# PWR_BUCK.net
KiCad netlist of a schematic drawn in Altium Designer
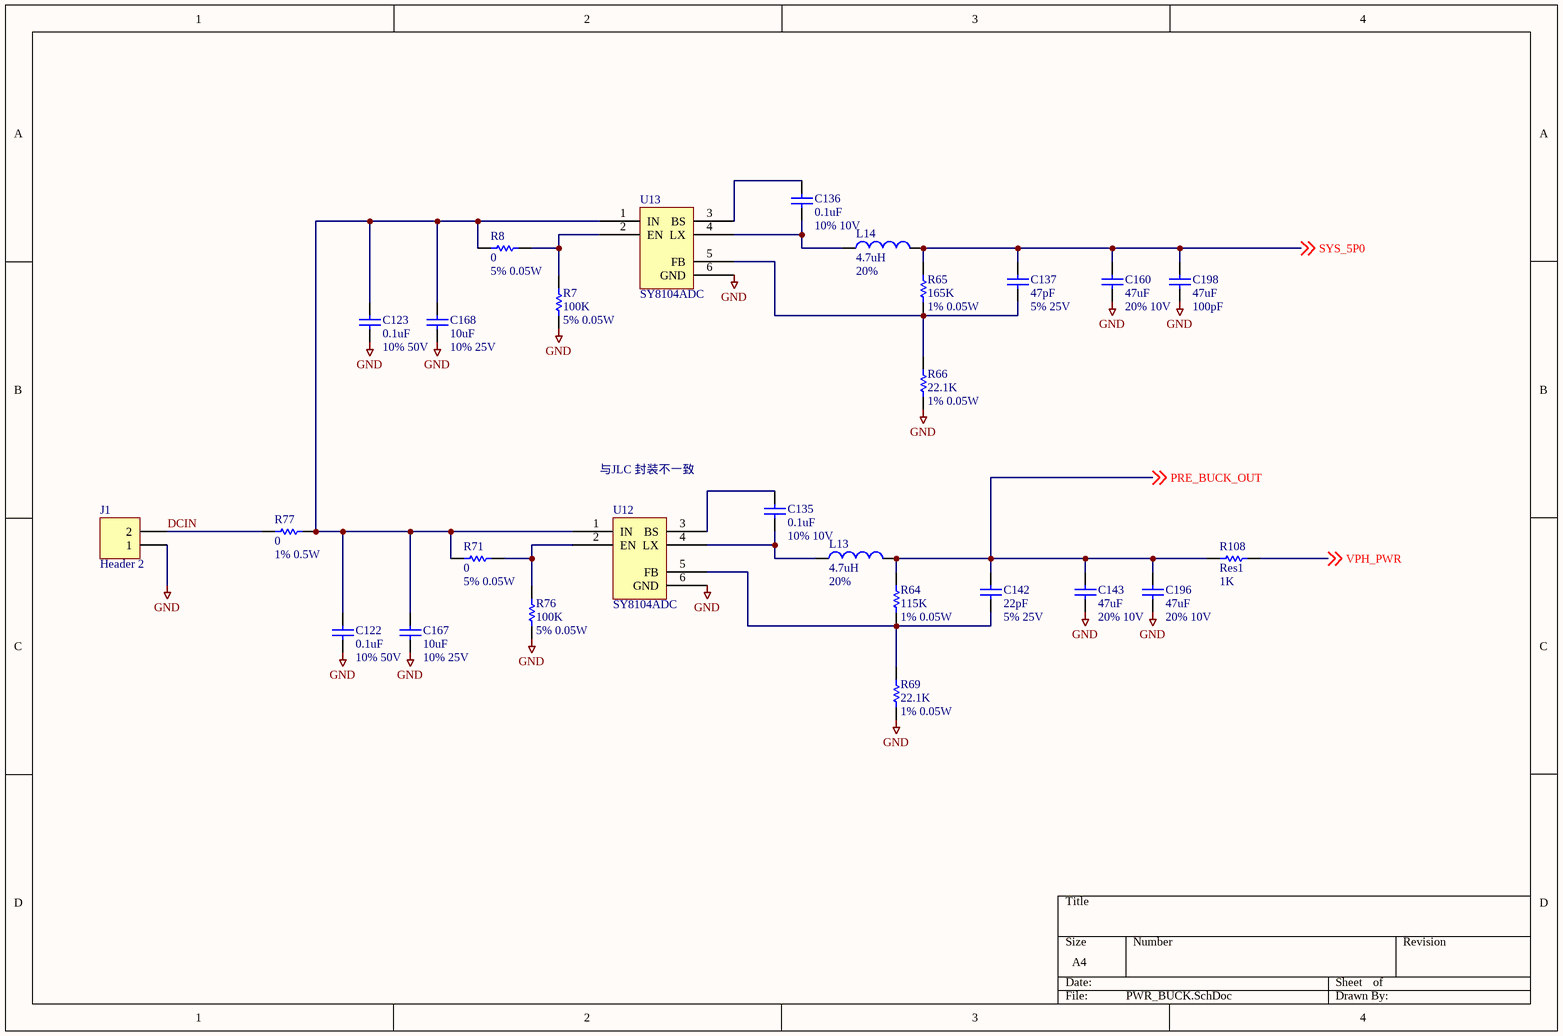
[diagram p0: PWR_BUCK.SchDoc]

(export (version "E")
  (design (tool "Eeschema 10.0.6"))
  (components
    (comp (ref "C122")
      (value "0.1uF")
      (footprint "RAD-0.3")
      (description "Capacitor")
      (fields (field (name "ALTIUM_VALUE") "10% 50V") (field (name "PUBLISHER") "Altium Limited"))
      (libsource (lib "Miscellaneous Devices") (part "Cap"))
    )
    (comp (ref "C123")
      (value "0.1uF")
      (footprint "RAD-0.3")
      (description "Capacitor")
      (fields (field (name "ALTIUM_VALUE") "10% 50V") (field (name "PUBLISHER") "Altium Limited"))
      (libsource (lib "Miscellaneous Devices") (part "Cap"))
    )
    (comp (ref "C135")
      (value "0.1uF")
      (footprint "RAD-0.3")
      (description "Capacitor")
      (fields (field (name "ALTIUM_VALUE") "10% 10V") (field (name "PUBLISHER") "Altium Limited"))
      (libsource (lib "Miscellaneous Devices") (part "Cap"))
    )
    (comp (ref "C136")
      (value "0.1uF")
      (footprint "RAD-0.3")
      (description "Capacitor")
      (fields (field (name "ALTIUM_VALUE") "10% 10V") (field (name "PUBLISHER") "Altium Limited"))
      (libsource (lib "Miscellaneous Devices") (part "Cap"))
    )
    (comp (ref "C137")
      (value "47pF")
      (footprint "RAD-0.3")
      (description "Capacitor")
      (fields (field (name "ALTIUM_VALUE") "5% 25V") (field (name "PUBLISHER") "Altium Limited"))
      (libsource (lib "Miscellaneous Devices") (part "Cap"))
    )
    (comp (ref "C142")
      (value "22pF")
      (footprint "RAD-0.3")
      (description "Capacitor")
      (fields (field (name "ALTIUM_VALUE") "5% 25V") (field (name "PUBLISHER") "Altium Limited"))
      (libsource (lib "Miscellaneous Devices") (part "Cap"))
    )
    (comp (ref "C143")
      (value "47uF")
      (footprint "RAD-0.3")
      (description "Capacitor")
      (fields (field (name "ALTIUM_VALUE") "20% 10V") (field (name "PUBLISHER") "Altium Limited"))
      (libsource (lib "Miscellaneous Devices") (part "Cap"))
    )
    (comp (ref "C160")
      (value "47uF")
      (footprint "RAD-0.3")
      (description "Capacitor")
      (fields (field (name "ALTIUM_VALUE") "20% 10V") (field (name "PUBLISHER") "Altium Limited"))
      (libsource (lib "Miscellaneous Devices") (part "Cap"))
    )
    (comp (ref "C167")
      (value "10uF")
      (footprint "RAD-0.3")
      (description "Capacitor")
      (fields (field (name "ALTIUM_VALUE") "10% 25V") (field (name "PUBLISHER") "Altium Limited"))
      (libsource (lib "Miscellaneous Devices") (part "Cap"))
    )
    (comp (ref "C168")
      (value "10uF")
      (footprint "RAD-0.3")
      (description "Capacitor")
      (fields (field (name "ALTIUM_VALUE") "10% 25V") (field (name "PUBLISHER") "Altium Limited"))
      (libsource (lib "Miscellaneous Devices") (part "Cap"))
    )
    (comp (ref "C196")
      (value "47uF")
      (footprint "RAD-0.3")
      (description "Capacitor")
      (fields (field (name "ALTIUM_VALUE") "20% 10V") (field (name "PUBLISHER") "Altium Limited"))
      (libsource (lib "Miscellaneous Devices") (part "Cap"))
    )
    (comp (ref "C198")
      (value "47uF")
      (footprint "RAD-0.3")
      (description "Capacitor")
      (fields (field (name "ALTIUM_VALUE") "100pF") (field (name "PUBLISHER") "Altium Limited"))
      (libsource (lib "Miscellaneous Devices") (part "Cap"))
    )
    (comp (ref "J1")
      (value "Header 2")
      (footprint "HDR1X2")
      (description "Header, 2-Pin")
      (fields (field (name "PUBLISHER") "Altium Limited"))
      (libsource (lib "Miscellaneous Connectors") (part "Header 2"))
    )
    (comp (ref "L13")
      (value "4.7uH")
      (footprint "0402-A")
      (description "Inductor")
      (fields (field (name "ALTIUM_VALUE") "20%") (field (name "PUBLISHER") "Altium Limited"))
      (libsource (lib "Miscellaneous Devices") (part "Inductor"))
    )
    (comp (ref "L14")
      (value "4.7uH")
      (footprint "0402-A")
      (description "Inductor")
      (fields (field (name "ALTIUM_VALUE") "20%") (field (name "PUBLISHER") "Altium Limited"))
      (libsource (lib "Miscellaneous Devices") (part "Inductor"))
    )
    (comp (ref "R7")
      (value "100K")
      (footprint "AXIAL-0.3")
      (description "Resistor")
      (fields (field (name "ALTIUM_VALUE") "5% 0.05W") (field (name "PUBLISHER") "Altium Limited"))
      (libsource (lib "Miscellaneous Devices") (part "Res1"))
    )
    (comp (ref "R8")
      (value "0")
      (footprint "AXIAL-0.3")
      (description "Resistor")
      (fields (field (name "ALTIUM_VALUE") "5% 0.05W") (field (name "PUBLISHER") "Altium Limited"))
      (libsource (lib "Miscellaneous Devices") (part "Res1"))
    )
    (comp (ref "R64")
      (value "115K")
      (footprint "AXIAL-0.3")
      (description "Resistor")
      (fields (field (name "ALTIUM_VALUE") "1% 0.05W") (field (name "PUBLISHER") "Altium Limited"))
      (libsource (lib "Miscellaneous Devices") (part "Res1"))
    )
    (comp (ref "R65")
      (value "165K")
      (footprint "AXIAL-0.3")
      (description "Resistor")
      (fields (field (name "ALTIUM_VALUE") "1% 0.05W") (field (name "PUBLISHER") "Altium Limited"))
      (libsource (lib "Miscellaneous Devices") (part "Res1"))
    )
    (comp (ref "R66")
      (value "22.1K")
      (footprint "AXIAL-0.3")
      (description "Resistor")
      (fields (field (name "ALTIUM_VALUE") "1% 0.05W") (field (name "PUBLISHER") "Altium Limited"))
      (libsource (lib "Miscellaneous Devices") (part "Res1"))
    )
    (comp (ref "R69")
      (value "22.1K")
      (footprint "AXIAL-0.3")
      (description "Resistor")
      (fields (field (name "ALTIUM_VALUE") "1% 0.05W") (field (name "PUBLISHER") "Altium Limited"))
      (libsource (lib "Miscellaneous Devices") (part "Res1"))
    )
    (comp (ref "R71")
      (value "0")
      (footprint "AXIAL-0.3")
      (description "Resistor")
      (fields (field (name "ALTIUM_VALUE") "5% 0.05W") (field (name "PUBLISHER") "Altium Limited"))
      (libsource (lib "Miscellaneous Devices") (part "Res1"))
    )
    (comp (ref "R76")
      (value "100K")
      (footprint "AXIAL-0.3")
      (description "Resistor")
      (fields (field (name "ALTIUM_VALUE") "5% 0.05W") (field (name "PUBLISHER") "Altium Limited"))
      (libsource (lib "Miscellaneous Devices") (part "Res1"))
    )
    (comp (ref "R77")
      (value "0")
      (footprint "AXIAL-0.3")
      (description "Resistor")
      (fields (field (name "ALTIUM_VALUE") "1% 0.5W") (field (name "PUBLISHER") "Altium Limited"))
      (libsource (lib "Miscellaneous Devices") (part "Res1"))
    )
    (comp (ref "R108")
      (value "Res1")
      (footprint "AXIAL-0.3")
      (description "Resistor")
      (fields (field (name "ALTIUM_VALUE") "1K") (field (name "PUBLISHER") "Altium Limited"))
      (libsource (lib "Miscellaneous Devices") (part "Res1"))
    )
    (comp (ref "U12")
      (value "SY8104ADC")
      (libsource (lib "MSM8916_DRAM_PMIC_REF_Library") (part "SY8104ADC"))
    )
    (comp (ref "U13")
      (value "SY8104ADC")
      (libsource (lib "MSM8916_DRAM_PMIC_REF_Library") (part "SY8104ADC"))
    )
  )
  (nets
    (net (code "1") (name "/DCIN") (class "Default")
      (node (ref "J1") (pin "2") (pinfunction "2_2") (pintype "passive"))
      (node (ref "R77") (pin "1") (pinfunction "1_1") (pintype "passive"))
    )
    (net (code "2") (name "GND") (class "Default")
      (node (ref "C122") (pin "1") (pinfunction "1_1") (pintype "passive"))
      (node (ref "C123") (pin "1") (pinfunction "1_1") (pintype "passive"))
      (node (ref "C143") (pin "1") (pinfunction "1_1") (pintype "passive"))
      (node (ref "C160") (pin "1") (pinfunction "1_1") (pintype "passive"))
      (node (ref "C167") (pin "1") (pinfunction "1_1") (pintype "passive"))
      (node (ref "C168") (pin "1") (pinfunction "1_1") (pintype "passive"))
      (node (ref "C196") (pin "1") (pinfunction "1_1") (pintype "passive"))
      (node (ref "C198") (pin "1") (pinfunction "1_1") (pintype "passive"))
      (node (ref "J1") (pin "1") (pinfunction "1_1") (pintype "passive"))
      (node (ref "R66") (pin "1") (pinfunction "1_1") (pintype "passive"))
      (node (ref "R69") (pin "1") (pinfunction "1_1") (pintype "passive"))
      (node (ref "R7") (pin "1") (pinfunction "1_1") (pintype "passive"))
      (node (ref "R76") (pin "1") (pinfunction "1_1") (pintype "passive"))
      (node (ref "U12") (pin "6") (pinfunction "GND_6") (pintype "passive"))
      (node (ref "U13") (pin "6") (pinfunction "GND_6") (pintype "passive"))
    )
    (net (code "3") (name "Net-(U12-BS)") (class "Default")
      (node (ref "C135") (pin "2") (pinfunction "2_2") (pintype "passive"))
      (node (ref "U12") (pin "3") (pinfunction "BS_3") (pintype "passive"))
    )
    (net (code "4") (name "Net-(U12-EN)") (class "Default")
      (node (ref "R71") (pin "2") (pinfunction "2_2") (pintype "passive"))
      (node (ref "R76") (pin "2") (pinfunction "2_2") (pintype "passive"))
      (node (ref "U12") (pin "2") (pinfunction "EN_2") (pintype "passive"))
    )
    (net (code "5") (name "Net-(U12-FB)") (class "Default")
      (node (ref "C142") (pin "1") (pinfunction "1_1") (pintype "passive"))
      (node (ref "R64") (pin "1") (pinfunction "1_1") (pintype "passive"))
      (node (ref "R69") (pin "2") (pinfunction "2_2") (pintype "passive"))
      (node (ref "U12") (pin "5") (pinfunction "FB_5") (pintype "passive"))
    )
    (net (code "6") (name "Net-(U12-IN)") (class "Default")
      (node (ref "C122") (pin "2") (pinfunction "2_2") (pintype "passive"))
      (node (ref "C123") (pin "2") (pinfunction "2_2") (pintype "passive"))
      (node (ref "C167") (pin "2") (pinfunction "2_2") (pintype "passive"))
      (node (ref "C168") (pin "2") (pinfunction "2_2") (pintype "passive"))
      (node (ref "R71") (pin "1") (pinfunction "1_1") (pintype "passive"))
      (node (ref "R77") (pin "2") (pinfunction "2_2") (pintype "passive"))
      (node (ref "R8") (pin "1") (pinfunction "1_1") (pintype "passive"))
      (node (ref "U12") (pin "1") (pinfunction "IN_1") (pintype "passive"))
      (node (ref "U13") (pin "1") (pinfunction "IN_1") (pintype "passive"))
    )
    (net (code "7") (name "Net-(U12-LX)") (class "Default")
      (node (ref "C135") (pin "1") (pinfunction "1_1") (pintype "passive"))
      (node (ref "L13") (pin "1") (pinfunction "1_1") (pintype "passive"))
      (node (ref "U12") (pin "4") (pinfunction "LX_4") (pintype "passive"))
    )
    (net (code "8") (name "Net-(U13-BS)") (class "Default")
      (node (ref "C136") (pin "2") (pinfunction "2_2") (pintype "passive"))
      (node (ref "U13") (pin "3") (pinfunction "BS_3") (pintype "passive"))
    )
    (net (code "9") (name "Net-(U13-EN)") (class "Default")
      (node (ref "R7") (pin "2") (pinfunction "2_2") (pintype "passive"))
      (node (ref "R8") (pin "2") (pinfunction "2_2") (pintype "passive"))
      (node (ref "U13") (pin "2") (pinfunction "EN_2") (pintype "passive"))
    )
    (net (code "10") (name "Net-(U13-FB)") (class "Default")
      (node (ref "C137") (pin "1") (pinfunction "1_1") (pintype "passive"))
      (node (ref "R65") (pin "1") (pinfunction "1_1") (pintype "passive"))
      (node (ref "R66") (pin "2") (pinfunction "2_2") (pintype "passive"))
      (node (ref "U13") (pin "5") (pinfunction "FB_5") (pintype "passive"))
    )
    (net (code "11") (name "Net-(U13-LX)") (class "Default")
      (node (ref "C136") (pin "1") (pinfunction "1_1") (pintype "passive"))
      (node (ref "L14") (pin "1") (pinfunction "1_1") (pintype "passive"))
      (node (ref "U13") (pin "4") (pinfunction "LX_4") (pintype "passive"))
    )
    (net (code "12") (name "PRE_BUCK_OUT") (class "Default")
      (node (ref "C142") (pin "2") (pinfunction "2_2") (pintype "passive"))
      (node (ref "C143") (pin "2") (pinfunction "2_2") (pintype "passive"))
      (node (ref "C196") (pin "2") (pinfunction "2_2") (pintype "passive"))
      (node (ref "L13") (pin "2") (pinfunction "2_2") (pintype "passive"))
      (node (ref "R108") (pin "1") (pinfunction "1_1") (pintype "passive"))
      (node (ref "R64") (pin "2") (pinfunction "2_2") (pintype "passive"))
    )
    (net (code "13") (name "SYS_5P0") (class "Default")
      (node (ref "C137") (pin "2") (pinfunction "2_2") (pintype "passive"))
      (node (ref "C160") (pin "2") (pinfunction "2_2") (pintype "passive"))
      (node (ref "C198") (pin "2") (pinfunction "2_2") (pintype "passive"))
      (node (ref "L14") (pin "2") (pinfunction "2_2") (pintype "passive"))
      (node (ref "R65") (pin "2") (pinfunction "2_2") (pintype "passive"))
    )
    (net (code "14") (name "VPH_PWR") (class "Default")
      (node (ref "R108") (pin "2") (pinfunction "2_2") (pintype "passive"))
    )
  )
)
